# 28Pins_Schematic_V1I1.net
KiCad netlist of a schematic drawn in Altium Designer
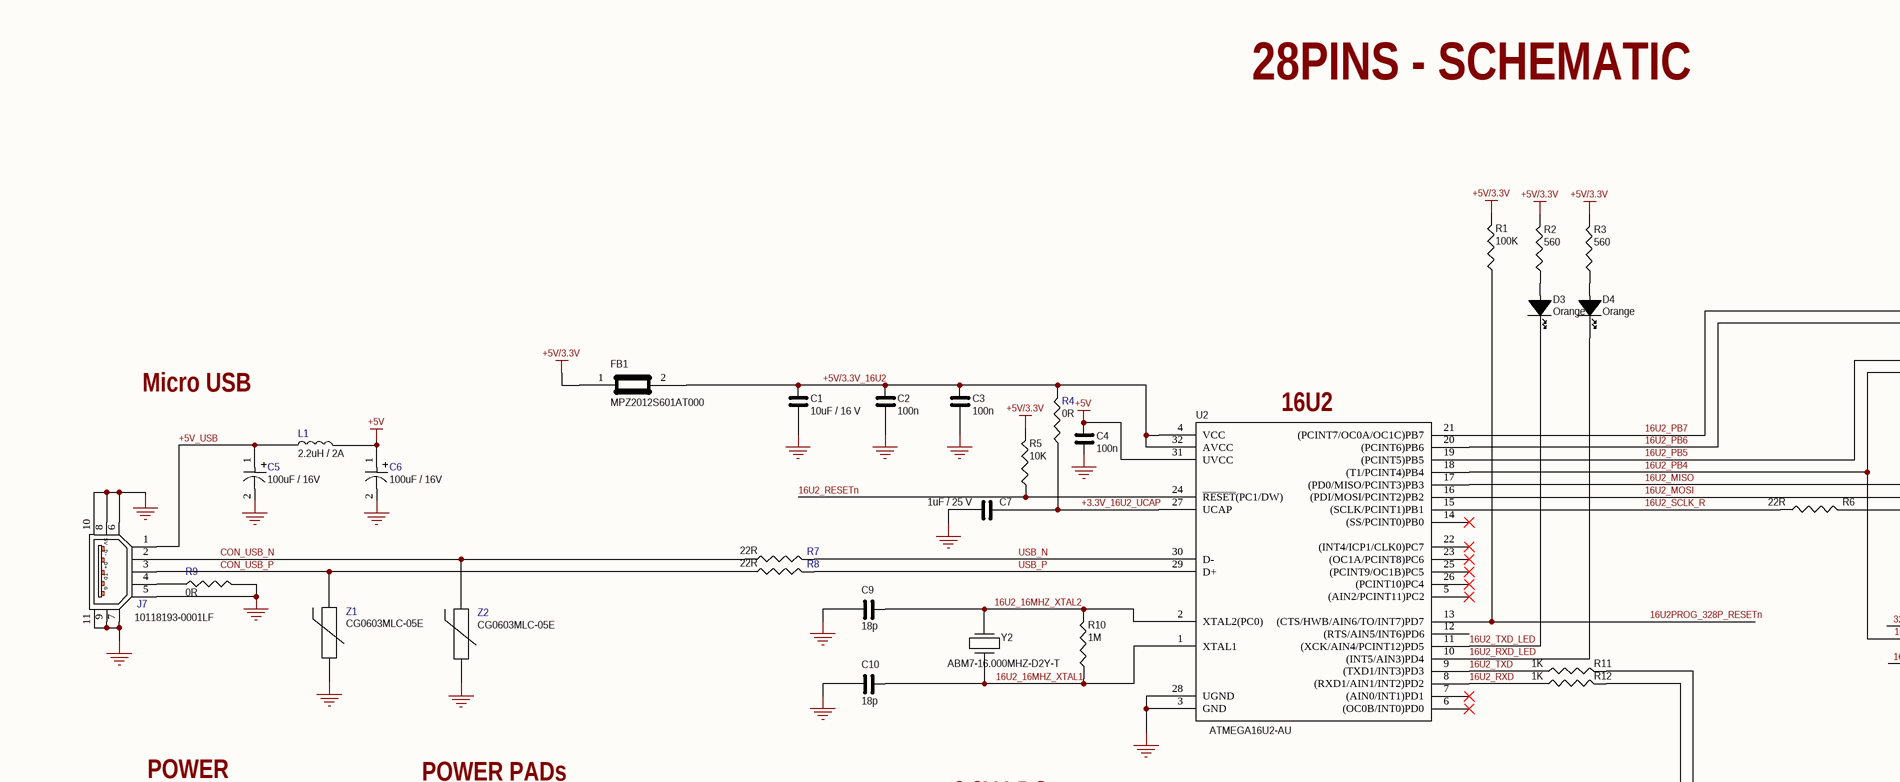
[diagram p0: 28Pins_Schematic_V1I1.SchDoc, top left]
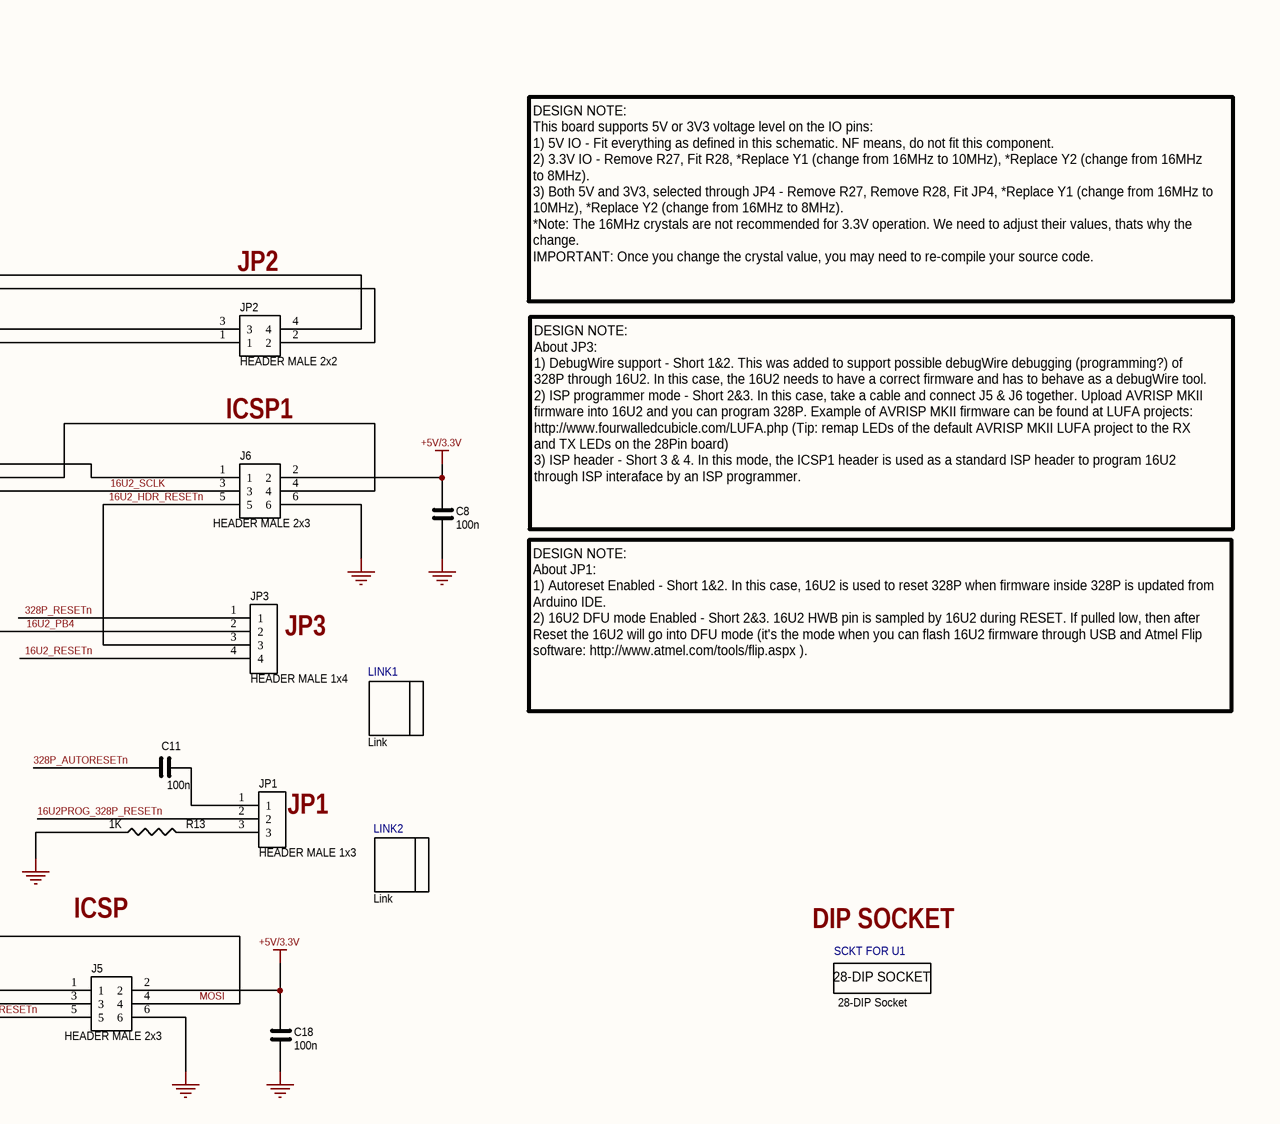
[diagram p1: 28Pins_Schematic_V1I1.SchDoc, top right]
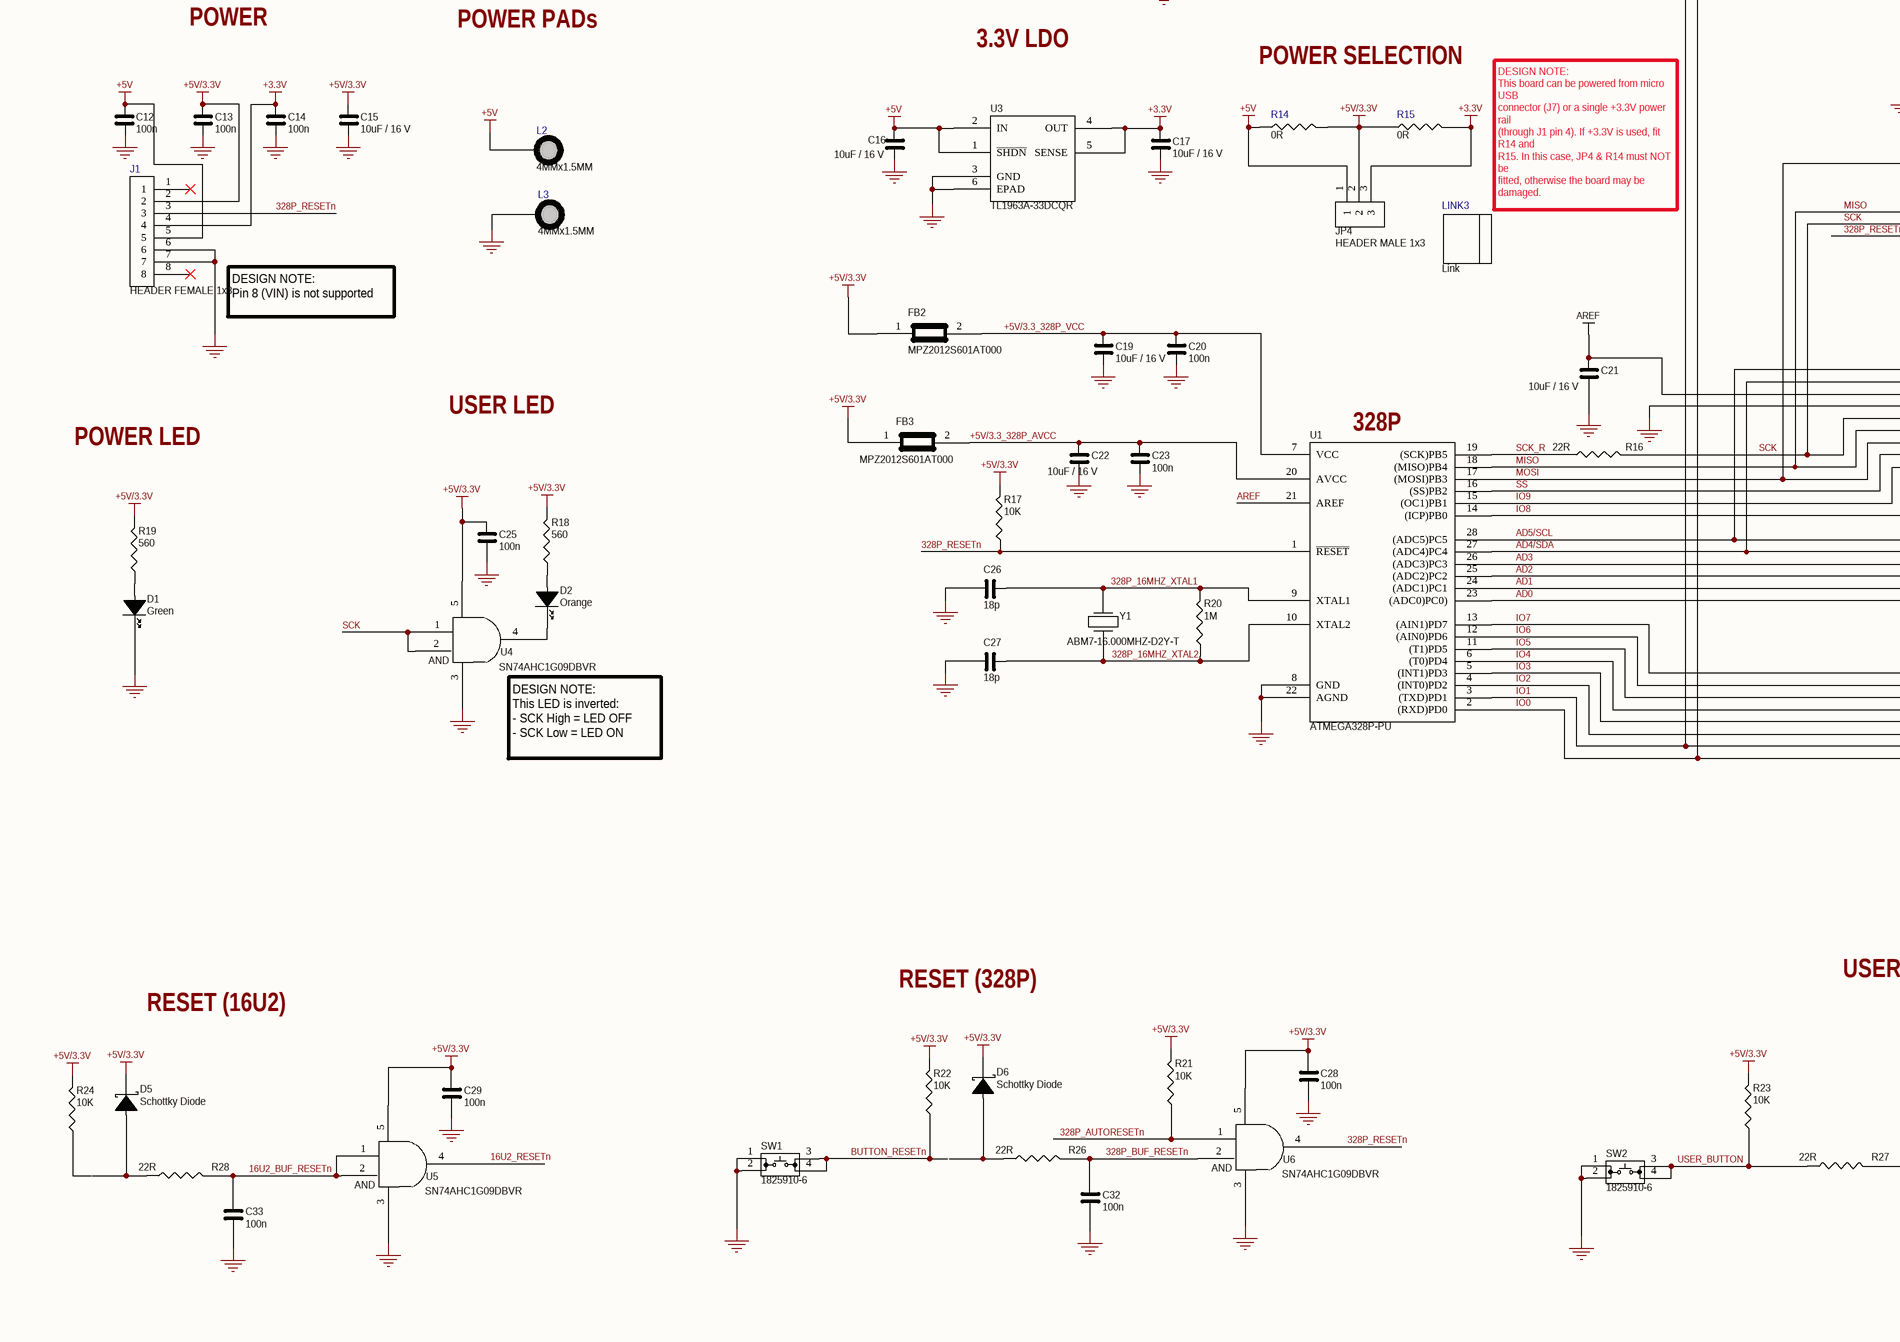
[diagram p2: 28Pins_Schematic_V1I1.SchDoc, bottom left]
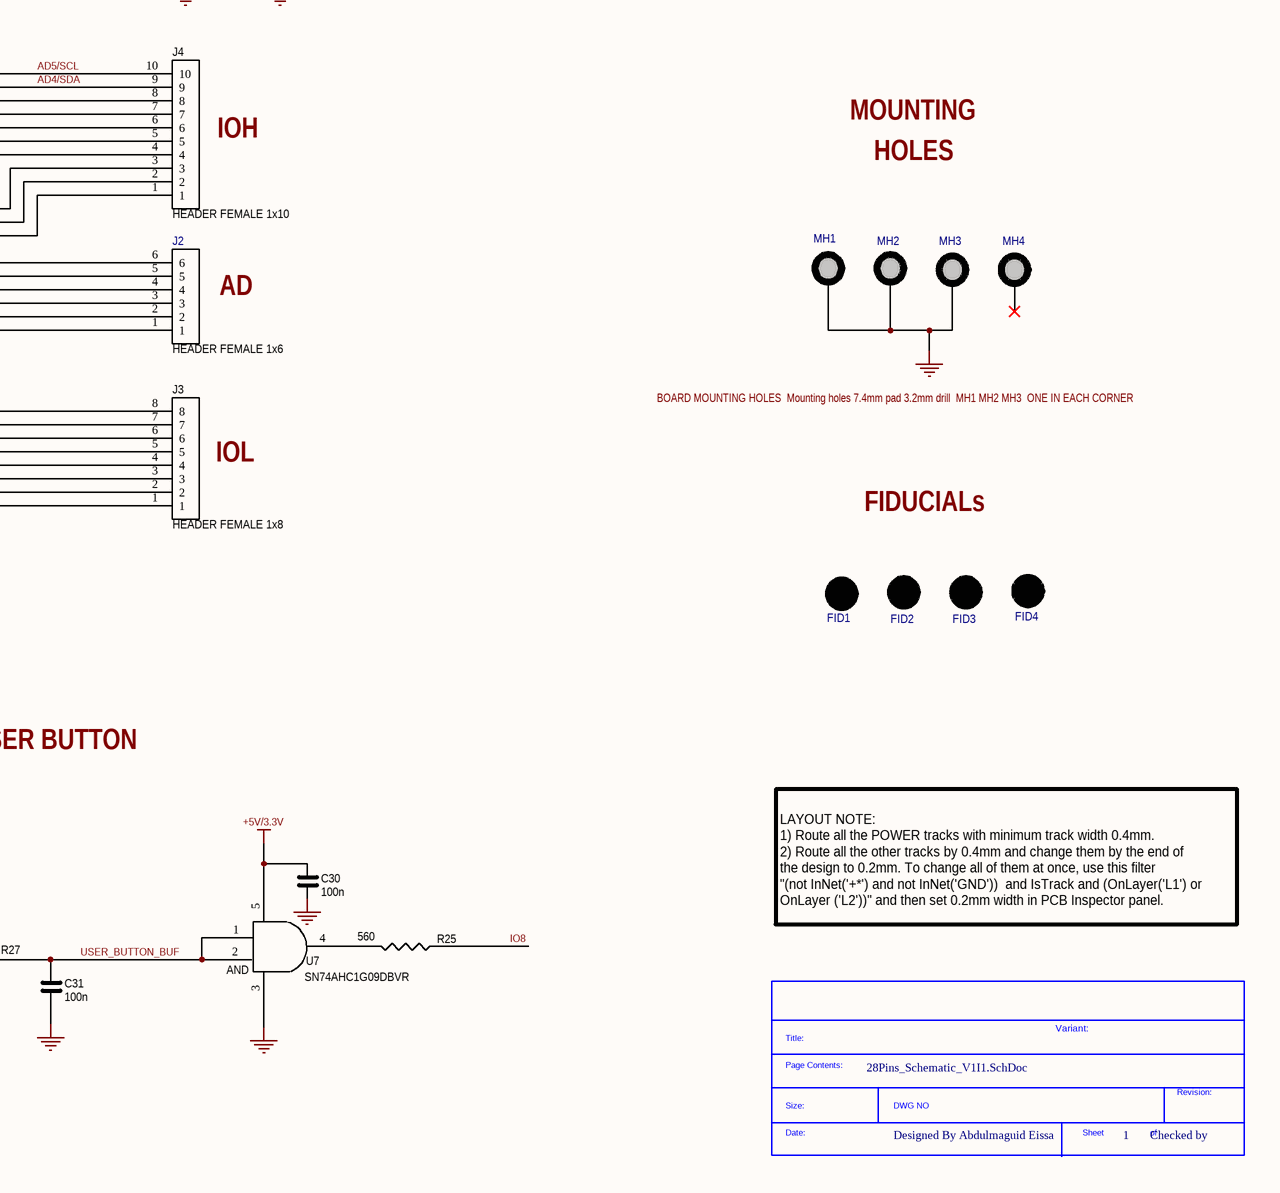
[diagram p3: 28Pins_Schematic_V1I1.SchDoc, bottom right]

(export (version "E")
  (design (tool "Eeschema 10.0.6"))
  (components
    (comp (ref "*") (value "SDTitleBlock") (libsource (lib "*") (part "SDTitleBlock")))
    (comp (ref "C1")
      (value "10uF / 16 V")
      (footprint "C0805")
      (libsource (lib "28Pins_Schematic_Lib") (part "10uF_CAP"))
    )
    (comp (ref "C2")
      (value "100n")
      (footprint "C0805")
      (libsource (lib "28Pins_Schematic_Lib") (part "0.1uF_CAP"))
    )
    (comp (ref "C3")
      (value "100n")
      (footprint "C0805")
      (libsource (lib "28Pins_Schematic_Lib") (part "0.1uF_CAP"))
    )
    (comp (ref "C4")
      (value "100n")
      (footprint "C0805")
      (libsource (lib "28Pins_Schematic_Lib") (part "0.1uF_CAP"))
    )
    (comp (ref "C5")
      (value "100uF / 16V")
      (footprint "C_ALU_C_SIZE")
      (libsource (lib "28Pins_Schematic_Lib") (part "100uF_PCAP"))
    )
    (comp (ref "C6")
      (value "100uF / 16V")
      (footprint "C_ALU_C_SIZE")
      (libsource (lib "28Pins_Schematic_Lib") (part "100uF_PCAP"))
    )
    (comp (ref "C7")
      (value "1uF / 25 V")
      (footprint "C0805")
      (libsource (lib "28Pins_Schematic_Lib") (part "1uF_CAP"))
    )
    (comp (ref "C8")
      (value "100n")
      (footprint "C0805")
      (libsource (lib "28Pins_Schematic_Lib") (part "0.1uF_CAP"))
    )
    (comp (ref "C9")
      (value "18p")
      (footprint "C0805")
      (libsource (lib "28Pins_Schematic_Lib") (part "18pF_CAP"))
    )
    (comp (ref "C10")
      (value "18p")
      (footprint "C0805")
      (libsource (lib "28Pins_Schematic_Lib") (part "18pF_CAP"))
    )
    (comp (ref "C11")
      (value "100n")
      (footprint "C0805")
      (libsource (lib "28Pins_Schematic_Lib") (part "0.1uF_CAP"))
    )
    (comp (ref "C12")
      (value "100n")
      (footprint "C0805")
      (libsource (lib "28Pins_Schematic_Lib") (part "0.1uF_CAP"))
    )
    (comp (ref "C13")
      (value "100n")
      (footprint "C0805")
      (libsource (lib "28Pins_Schematic_Lib") (part "0.1uF_CAP"))
    )
    (comp (ref "C14")
      (value "100n")
      (footprint "C0805")
      (libsource (lib "28Pins_Schematic_Lib") (part "0.1uF_CAP"))
    )
    (comp (ref "C15")
      (value "10uF / 16 V")
      (footprint "C0805")
      (libsource (lib "28Pins_Schematic_Lib") (part "10uF_CAP"))
    )
    (comp (ref "C16")
      (value "10uF / 16 V")
      (footprint "C0805")
      (libsource (lib "28Pins_Schematic_Lib") (part "10uF_CAP"))
    )
    (comp (ref "C17")
      (value "10uF / 16 V")
      (footprint "C0805")
      (libsource (lib "28Pins_Schematic_Lib") (part "10uF_CAP"))
    )
    (comp (ref "C18")
      (value "100n")
      (footprint "C0805")
      (libsource (lib "28Pins_Schematic_Lib") (part "0.1uF_CAP"))
    )
    (comp (ref "C19")
      (value "10uF / 16 V")
      (footprint "C0805")
      (libsource (lib "28Pins_Schematic_Lib") (part "10uF_CAP"))
    )
    (comp (ref "C20")
      (value "100n")
      (footprint "C0805")
      (libsource (lib "28Pins_Schematic_Lib") (part "0.1uF_CAP"))
    )
    (comp (ref "C21")
      (value "10uF / 16 V")
      (footprint "C0805")
      (libsource (lib "28Pins_Schematic_Lib") (part "10uF_CAP"))
    )
    (comp (ref "C22")
      (value "10uF / 16 V")
      (footprint "C0805")
      (libsource (lib "28Pins_Schematic_Lib") (part "10uF_CAP"))
    )
    (comp (ref "C23")
      (value "100n")
      (footprint "C0805")
      (libsource (lib "28Pins_Schematic_Lib") (part "0.1uF_CAP"))
    )
    (comp (ref "C25")
      (value "100n")
      (footprint "C0805")
      (libsource (lib "28Pins_Schematic_Lib") (part "0.1uF_CAP"))
    )
    (comp (ref "C26")
      (value "18p")
      (footprint "C0805")
      (libsource (lib "28Pins_Schematic_Lib") (part "18pF_CAP"))
    )
    (comp (ref "C27")
      (value "18p")
      (footprint "C0805")
      (libsource (lib "28Pins_Schematic_Lib") (part "18pF_CAP"))
    )
    (comp (ref "C28")
      (value "100n")
      (footprint "C0805")
      (libsource (lib "28Pins_Schematic_Lib") (part "0.1uF_CAP"))
    )
    (comp (ref "C29")
      (value "100n")
      (footprint "C0805")
      (libsource (lib "28Pins_Schematic_Lib") (part "0.1uF_CAP"))
    )
    (comp (ref "C30")
      (value "100n")
      (footprint "C0805")
      (libsource (lib "28Pins_Schematic_Lib") (part "0.1uF_CAP"))
    )
    (comp (ref "C31")
      (value "100n")
      (footprint "C0805")
      (libsource (lib "28Pins_Schematic_Lib") (part "0.1uF_CAP"))
    )
    (comp (ref "C32")
      (value "100n")
      (footprint "C0805")
      (libsource (lib "28Pins_Schematic_Lib") (part "0.1uF_CAP"))
    )
    (comp (ref "C33")
      (value "100n")
      (footprint "C0805")
      (libsource (lib "28Pins_Schematic_Lib") (part "0.1uF_CAP"))
    )
    (comp (ref "D1")
      (value "Green")
      (footprint "LED0603")
      (libsource (lib "28Pins_Schematic_Lib") (part "LED_Green"))
    )
    (comp (ref "D2")
      (value "Orange")
      (footprint "LED0603")
      (libsource (lib "28Pins_Schematic_Lib") (part "LED_Orange"))
    )
    (comp (ref "D3")
      (value "Orange")
      (footprint "LED0603")
      (libsource (lib "28Pins_Schematic_Lib") (part "LED_Orange"))
    )
    (comp (ref "D4")
      (value "Orange")
      (footprint "LED0603")
      (libsource (lib "28Pins_Schematic_Lib") (part "LED_Orange"))
    )
    (comp (ref "D5")
      (value "Schottky Diode")
      (footprint "SOD323")
      (description "Diode,Schottky Barrier,Fast,Vr 30V,If 200mA,Pkg SOD-323,Vf 0.52VDC,Trr 5ns")
      (fields
        (field (name "MANUFACTURER") "ON Semiconductor")
        (field (name "MANUFACTURER PART NUMBER") "BAT54HT1G")
      )
      (libsource (lib "28Pins_Schematic_Lib") (part "Schottky Diode"))
    )
    (comp (ref "D6")
      (value "Schottky Diode")
      (footprint "SOD323")
      (description "Diode,Schottky Barrier,Fast,Vr 30V,If 200mA,Pkg SOD-323,Vf 0.52VDC,Trr 5ns")
      (fields
        (field (name "MANUFACTURER") "ON Semiconductor")
        (field (name "MANUFACTURER PART NUMBER") "BAT54HT1G")
      )
      (libsource (lib "28Pins_Schematic_Lib") (part "Schottky Diode"))
    )
    (comp (ref "FB1")
      (value "MPZ2012S601AT000")
      (footprint "C0805")
      (libsource (lib "28Pins_Schematic_Lib") (part "Ferrite_Bead"))
    )
    (comp (ref "FB2")
      (value "MPZ2012S601AT000")
      (footprint "C0805")
      (libsource (lib "28Pins_Schematic_Lib") (part "Ferrite_Bead"))
    )
    (comp (ref "FB3")
      (value "MPZ2012S601AT000")
      (footprint "C0805")
      (libsource (lib "28Pins_Schematic_Lib") (part "Ferrite_Bead"))
    )
    (comp (ref "FID1")
      (value "FID_1mm")
      (footprint "FID_40x1120")
      (description "Fiducial 40mil diameter")
      (libsource (lib "28Pins_Schematic_Lib") (part "Fiducial"))
    )
    (comp (ref "FID2")
      (value "FID_1mm")
      (footprint "FID_40x1120")
      (description "Fiducial 40mil diameter")
      (libsource (lib "28Pins_Schematic_Lib") (part "Fiducial"))
    )
    (comp (ref "FID3")
      (value "FID_1mm")
      (footprint "FID_40x1120")
      (description "Fiducial 40mil diameter")
      (libsource (lib "28Pins_Schematic_Lib") (part "Fiducial"))
    )
    (comp (ref "FID4")
      (value "FID_1mm")
      (footprint "FID_40x1120")
      (description "Fiducial 40mil diameter")
      (libsource (lib "28Pins_Schematic_Lib") (part "Fiducial"))
    )
    (comp (ref "J1")
      (value "HEADER FEMALE 1x8")
      (footprint "1x8PIN_FEMALE_HDR")
      (libsource (lib "") (part "1x8Pin_Female_Hdr_1"))
    )
    (comp (ref "J2")
      (value "HEADER FEMALE 1x6")
      (footprint "1x6PIN_FEMALE_HDR")
      (libsource (lib "28Pins_Schematic_Lib") (part "1x6Pin_Female_Hdr"))
    )
    (comp (ref "J3")
      (value "HEADER FEMALE 1x8")
      (footprint "1x8PIN_FEMALE_HDR")
      (libsource (lib "28Pins_Schematic_Lib") (part "1x8Pin_Female_Hdr"))
    )
    (comp (ref "J4")
      (value "HEADER FEMALE 1x10")
      (footprint "1x10PIN_FEMALE_HDR")
      (libsource (lib "28Pins_Schematic_Lib") (part "10Pin_Female_Hdr"))
    )
    (comp (ref "J5")
      (value "HEADER MALE 2x3")
      (footprint "2x3PIN_MALE_HDR")
      (libsource (lib "28Pins_Schematic_Lib") (part "2x3Pin_Male_Hdr"))
    )
    (comp (ref "J6")
      (value "HEADER MALE 2x3")
      (footprint "2x3PIN_MALE_HDR")
      (libsource (lib "28Pins_Schematic_Lib") (part "2x3Pin_Male_Hdr"))
    )
    (comp (ref "J7")
      (value "10118193-0001LF")
      (footprint "USB_SOP")
      (description "Right Angle Surface Mount Mount Female USB Connector 100 V ac 1.8A")
      (fields (field (name "MANUFACTURER") "Amphenol ICC"))
      (libsource (lib "28Pins_Schematic_Lib") (part "10118193-0001LF"))
    )
    (comp (ref "JP1")
      (value "HEADER MALE 1x3")
      (footprint "1x3PIN_MALE_HDR")
      (libsource (lib "") (part "1x3Pin_Male_Hdr_1"))
    )
    (comp (ref "JP2")
      (value "HEADER MALE 2x2")
      (footprint "2x2PIN_MALE_HDR")
      (libsource (lib "28Pins_Schematic_Lib") (part "2x2Pin_Male_Hdr"))
    )
    (comp (ref "JP3")
      (value "HEADER MALE 1x4")
      (footprint "1x4PIN_MALE_HDR")
      (libsource (lib "28Pins_Schematic_Lib") (part "1x4Pin_Male_Hdr"))
    )
    (comp (ref "JP4")
      (value "HEADER MALE 1x3")
      (footprint "1x3PIN_MALE_HDR")
      (libsource (lib "28Pins_Schematic_Lib") (part "1x3Pin_Male_Hdr"))
    )
    (comp (ref "L1")
      (value "2.2uH / 2A")
      (footprint "L1210")
      (description "Inductor")
      (libsource (lib "28Pins_Schematic_Lib") (part "L1210R2R2MDWIT"))
    )
    (comp (ref "L2")
      (value "4MMx1.5MM")
      (footprint "PADS_WITH_WHOLE_4mmx1.5mm")
      (libsource (lib "28Pins_Schematic_Lib") (part "PAD_WITH_WHOLE_4MMx1.5MM"))
    )
    (comp (ref "L3")
      (value "4MMx1.5MM")
      (footprint "PADS_WITH_WHOLE_4mmx1.5mm")
      (libsource (lib "28Pins_Schematic_Lib") (part "PAD_WITH_WHOLE_4MMx1.5MM"))
    )
    (comp (ref "LINK1")
      (value "Link")
      (description "CONN JUMPER")
      (libsource (lib "28Pins_Schematic_Lib") (part "Link"))
    )
    (comp (ref "LINK2")
      (value "Link")
      (description "CONN JUMPER")
      (libsource (lib "28Pins_Schematic_Lib") (part "Link"))
    )
    (comp (ref "LINK3")
      (value "Link")
      (description "CONN JUMPER")
      (libsource (lib "28Pins_Schematic_Lib") (part "Link"))
    )
    (comp (ref "MH1")
      (value "Mounting Whole 3.4mmx3.2mm")
      (footprint "MOUNTING_WHOLE_NON_COPPER")
      (libsource (lib "28Pins_Schematic_Lib") (part "MOUNTING_WHOLE_NON_COPPER"))
    )
    (comp (ref "MH2")
      (value "Mounting Whole 3.4mmx3.2mm")
      (footprint "MOUNTING_WHOLE_NON_COPPER")
      (libsource (lib "28Pins_Schematic_Lib") (part "MOUNTING_WHOLE_NON_COPPER"))
    )
    (comp (ref "MH3")
      (value "Mounting Whole 3.4mmx3.2mm")
      (footprint "MOUNTING_WHOLE_NON_COPPER")
      (libsource (lib "28Pins_Schematic_Lib") (part "MOUNTING_WHOLE_NON_COPPER"))
    )
    (comp (ref "MH4")
      (value "Mounting Whole 3.4mmx3.2mm")
      (footprint "MOUNTING_WHOLE_NON_COPPER")
      (libsource (lib "28Pins_Schematic_Lib") (part "MOUNTING_WHOLE_NON_COPPER"))
    )
    (comp (ref "R1")
      (value "100K")
      (footprint "R0805")
      (libsource (lib "28Pins_Schematic_Lib") (part "100K_Resistor"))
    )
    (comp (ref "R2")
      (value "560")
      (footprint "R0805")
      (libsource (lib "28Pins_Schematic_Lib") (part "560_Resistor"))
    )
    (comp (ref "R3")
      (value "560")
      (footprint "R0805")
      (libsource (lib "28Pins_Schematic_Lib") (part "560_Resistor"))
    )
    (comp (ref "R4")
      (value "0R")
      (footprint "R0805")
      (libsource (lib "28Pins_Schematic_Lib") (part "0R_Resistor"))
    )
    (comp (ref "R5")
      (value "10K")
      (footprint "R0805")
      (libsource (lib "28Pins_Schematic_Lib") (part "10K_Resistor"))
    )
    (comp (ref "R6")
      (value "22R")
      (footprint "R0805")
      (libsource (lib "28Pins_Schematic_Lib") (part "22_Resistor"))
    )
    (comp (ref "R7")
      (value "22R")
      (footprint "R0805")
      (libsource (lib "28Pins_Schematic_Lib") (part "22_Resistor"))
    )
    (comp (ref "R8")
      (value "22R")
      (footprint "R0805")
      (libsource (lib "28Pins_Schematic_Lib") (part "22_Resistor"))
    )
    (comp (ref "R9")
      (value "0R")
      (footprint "R0805")
      (libsource (lib "28Pins_Schematic_Lib") (part "0R_Resistor"))
    )
    (comp (ref "R10")
      (value "1M")
      (footprint "R0805")
      (libsource (lib "28Pins_Schematic_Lib") (part "1M_Resistor"))
    )
    (comp (ref "R11")
      (value "1K")
      (footprint "R0805")
      (libsource (lib "28Pins_Schematic_Lib") (part "1K_Resistor"))
    )
    (comp (ref "R12")
      (value "1K")
      (footprint "R0805")
      (libsource (lib "28Pins_Schematic_Lib") (part "1K_Resistor"))
    )
    (comp (ref "R13")
      (value "1K")
      (footprint "R0805")
      (libsource (lib "28Pins_Schematic_Lib") (part "1K_Resistor"))
    )
    (comp (ref "R14")
      (value "0R")
      (footprint "R0805")
      (libsource (lib "28Pins_Schematic_Lib") (part "0R_Resistor"))
    )
    (comp (ref "R15")
      (value "0R")
      (footprint "R0805")
      (libsource (lib "28Pins_Schematic_Lib") (part "0R_Resistor"))
    )
    (comp (ref "R16")
      (value "22R")
      (footprint "R0805")
      (libsource (lib "28Pins_Schematic_Lib") (part "22_Resistor"))
    )
    (comp (ref "R17")
      (value "10K")
      (footprint "R0805")
      (libsource (lib "28Pins_Schematic_Lib") (part "10K_Resistor"))
    )
    (comp (ref "R18")
      (value "560")
      (footprint "R0805")
      (libsource (lib "28Pins_Schematic_Lib") (part "560_Resistor"))
    )
    (comp (ref "R19")
      (value "560")
      (footprint "R0805")
      (libsource (lib "28Pins_Schematic_Lib") (part "560_Resistor"))
    )
    (comp (ref "R20")
      (value "1M")
      (footprint "R0805")
      (libsource (lib "28Pins_Schematic_Lib") (part "1M_Resistor"))
    )
    (comp (ref "R21")
      (value "10K")
      (footprint "R0805")
      (libsource (lib "28Pins_Schematic_Lib") (part "10K_Resistor"))
    )
    (comp (ref "R22")
      (value "10K")
      (footprint "R0805")
      (libsource (lib "28Pins_Schematic_Lib") (part "10K_Resistor"))
    )
    (comp (ref "R23")
      (value "10K")
      (footprint "R0805")
      (libsource (lib "28Pins_Schematic_Lib") (part "10K_Resistor"))
    )
    (comp (ref "R24")
      (value "10K")
      (footprint "R0805")
      (libsource (lib "28Pins_Schematic_Lib") (part "10K_Resistor"))
    )
    (comp (ref "R25")
      (value "560")
      (footprint "R0805")
      (libsource (lib "28Pins_Schematic_Lib") (part "560_Resistor"))
    )
    (comp (ref "R26")
      (value "22R")
      (footprint "R0805")
      (libsource (lib "28Pins_Schematic_Lib") (part "22_Resistor"))
    )
    (comp (ref "R27")
      (value "22R")
      (footprint "R0805")
      (libsource (lib "28Pins_Schematic_Lib") (part "22_Resistor"))
    )
    (comp (ref "R28")
      (value "22R")
      (footprint "R0805")
      (libsource (lib "28Pins_Schematic_Lib") (part "22_Resistor"))
    )
    (comp (ref "SCKT FOR U1")
      (value "28-DIP Socket")
      (footprint "28-DIP_SCKT")
      (libsource (lib "28Pins_Schematic_Lib") (part "28Pin_DIP"))
    )
    (comp (ref "SW1")
      (value "1825910-6")
      (footprint "4PIN_BUTTON")
      (description "Push_Button")
      (libsource (lib "28Pins_Schematic_Lib") (part "4Pin_Push_Button"))
    )
    (comp (ref "SW2")
      (value "1825910-6")
      (footprint "4PIN_BUTTON")
      (description "Push_Button")
      (libsource (lib "28Pins_Schematic_Lib") (part "4Pin_Push_Button"))
    )
    (comp (ref "U1")
      (value "ATMEGA328P-PU")
      (footprint "28_DIP_U1")
      (description "ATMEGA328P-PU; 8 bit Microcontroller AVR 20MHz 1; 32kb Flash; 2kb RAM; I2C SPI 2")
      (fields (field (name "MANUFACTURER") "Microchip Technology Inc."))
      (libsource (lib "28Pins_Schematic_Lib") (part "ATMEGA328P-PU"))
    )
    (comp (ref "U2")
      (value "ATMEGA16U2-AU")
      (footprint "TQFP32")
      (libsource (lib "28Pins_Schematic_Lib") (part "ATMEGA16U2-AU"))
    )
    (comp (ref "U3")
      (value "TL1963A-33DCQR")
      (footprint "DCQR R-PDSO-G6")
      (libsource (lib "28Pins_Schematic_Lib") (part "Regulator"))
    )
    (comp (ref "U4")
      (value "SN74AHC1G09DBVR")
      (footprint "DBV_SOP_23_5")
      (libsource (lib "28Pins_Schematic_Lib") (part "AND gate"))
    )
    (comp (ref "U5")
      (value "SN74AHC1G09DBVR")
      (footprint "DBV_SOP_23_5")
      (libsource (lib "28Pins_Schematic_Lib") (part "AND gate"))
    )
    (comp (ref "U6")
      (value "SN74AHC1G09DBVR")
      (footprint "DBV_SOP_23_5")
      (libsource (lib "28Pins_Schematic_Lib") (part "AND gate"))
    )
    (comp (ref "U7")
      (value "SN74AHC1G09DBVR")
      (footprint "DBV_SOP_23_5")
      (libsource (lib "28Pins_Schematic_Lib") (part "AND gate"))
    )
    (comp (ref "Y1")
      (value "ABM7-16.000MHZ-D2Y-T")
      (footprint "AMB7_V1")
      (description "Crystal; Ceramic; 16.000MHZ; 18pf; 20ppm @ 25C; 30ppm -40+85C; 6.0 x 3.5 x 1.2mm; T/R")
      (fields (field (name "MANUFACTURER") "Abracon"))
      (libsource (lib "28Pins_Schematic_Lib") (part "ABM7-16.000MHZ-D2Y-T"))
    )
    (comp (ref "Y2")
      (value "ABM7-16.000MHZ-D2Y-T")
      (footprint "AMB7_V1")
      (description "Crystal; Ceramic; 16.000MHZ; 18pf; 20ppm @ 25C; 30ppm -40+85C; 6.0 x 3.5 x 1.2mm; T/R")
      (fields (field (name "MANUFACTURER") "Abracon"))
      (libsource (lib "28Pins_Schematic_Lib") (part "ABM7-16.000MHZ-D2Y-T"))
    )
    (comp (ref "Z1")
      (value "CG0603MLC-05E")
      (footprint "R0603")
      (description "Varistor; ESD Clamp Protector; 5 VDC; 20 Vclamp; IEC 61000-4-2 Level 4; 0603 SMD")
      (fields (field (name "MANUFACTURER") "Bourns"))
      (libsource (lib "28Pins_Schematic_Lib") (part "CG0603MLC-05E"))
    )
    (comp (ref "Z2")
      (value "CG0603MLC-05E")
      (footprint "R0603")
      (description "Varistor; ESD Clamp Protector; 5 VDC; 20 Vclamp; IEC 61000-4-2 Level 4; 0603 SMD")
      (fields (field (name "MANUFACTURER") "Bourns"))
      (libsource (lib "28Pins_Schematic_Lib") (part "CG0603MLC-05E"))
    )
  )
  (nets
    (net (code "1") (name "+3.3V") (class "Default")
      (node (ref "C14") (pin "2") (pinfunction "2_2") (pintype "passive"))
      (node (ref "C17") (pin "2") (pinfunction "2_2") (pintype "passive"))
      (node (ref "J1") (pin "4") (pinfunction "4_4") (pintype "passive"))
      (node (ref "JP4") (pin "3") (pinfunction "3_3") (pintype "passive"))
      (node (ref "R15") (pin "2") (pinfunction "2_2") (pintype "passive"))
      (node (ref "U3") (pin "4") (pinfunction "OUT_4") (pintype "passive"))
      (node (ref "U3") (pin "5") (pinfunction "SENSE_5") (pintype "passive"))
    )
    (net (code "2") (name "+5V") (class "Default")
      (node (ref "C12") (pin "1") (pinfunction "1_1") (pintype "passive"))
      (node (ref "C16") (pin "2") (pinfunction "2_2") (pintype "passive"))
      (node (ref "C4") (pin "2") (pinfunction "2_2") (pintype "passive"))
      (node (ref "C6") (pin "1") (pinfunction "1_1") (pintype "passive"))
      (node (ref "J1") (pin "5") (pinfunction "5_5") (pintype "passive"))
      (node (ref "JP4") (pin "1") (pinfunction "1_1") (pintype "passive"))
      (node (ref "L1") (pin "2") (pinfunction "2_2") (pintype "passive"))
      (node (ref "L2") (pin "1") (pinfunction "1_1") (pintype "passive"))
      (node (ref "R14") (pin "1") (pinfunction "1_1") (pintype "passive"))
      (node (ref "U2") (pin "31") (pinfunction "UVCC_31") (pintype "passive"))
      (node (ref "U3") (pin "1") (pinfunction "~{SHDN}_1") (pintype "passive"))
      (node (ref "U3") (pin "2") (pinfunction "IN_2") (pintype "passive"))
    )
    (net (code "3") (name "+5V{slash}3.3V") (class "Default")
      (node (ref "C13") (pin "2") (pinfunction "2_2") (pintype "passive"))
      (node (ref "C15") (pin "2") (pinfunction "2_2") (pintype "passive"))
      (node (ref "C18") (pin "2") (pinfunction "2_2") (pintype "passive"))
      (node (ref "C25") (pin "2") (pinfunction "2_2") (pintype "passive"))
      (node (ref "C28") (pin "2") (pinfunction "2_2") (pintype "passive"))
      (node (ref "C29") (pin "2") (pinfunction "2_2") (pintype "passive"))
      (node (ref "C30") (pin "2") (pinfunction "2_2") (pintype "passive"))
      (node (ref "C8") (pin "2") (pinfunction "2_2") (pintype "passive"))
      (node (ref "D5") (pin "1") (pinfunction "Cathode_1") (pintype "passive"))
      (node (ref "D6") (pin "1") (pinfunction "Cathode_1") (pintype "passive"))
      (node (ref "FB1") (pin "1") (pinfunction "1_1") (pintype "passive"))
      (node (ref "FB2") (pin "1") (pinfunction "1_1") (pintype "passive"))
      (node (ref "FB3") (pin "1") (pinfunction "1_1") (pintype "passive"))
      (node (ref "J1") (pin "2") (pinfunction "2_2") (pintype "passive"))
      (node (ref "J5") (pin "2") (pinfunction "2_2") (pintype "passive"))
      (node (ref "J6") (pin "2") (pinfunction "2_2") (pintype "passive"))
      (node (ref "JP4") (pin "2") (pinfunction "2_2") (pintype "passive"))
      (node (ref "R1") (pin "2") (pinfunction "2_2") (pintype "passive"))
      (node (ref "R14") (pin "2") (pinfunction "2_2") (pintype "passive"))
      (node (ref "R15") (pin "1") (pinfunction "1_1") (pintype "passive"))
      (node (ref "R17") (pin "2") (pinfunction "2_2") (pintype "passive"))
      (node (ref "R18") (pin "2") (pinfunction "2_2") (pintype "passive"))
      (node (ref "R19") (pin "2") (pinfunction "2_2") (pintype "passive"))
      (node (ref "R2") (pin "2") (pinfunction "2_2") (pintype "passive"))
      (node (ref "R21") (pin "2") (pinfunction "2_2") (pintype "passive"))
      (node (ref "R22") (pin "2") (pinfunction "2_2") (pintype "passive"))
      (node (ref "R23") (pin "2") (pinfunction "2_2") (pintype "passive"))
      (node (ref "R24") (pin "2") (pinfunction "2_2") (pintype "passive"))
      (node (ref "R3") (pin "2") (pinfunction "2_2") (pintype "passive"))
      (node (ref "R5") (pin "2") (pinfunction "2_2") (pintype "passive"))
      (node (ref "U4") (pin "5") (pinfunction "5_5") (pintype "passive"))
      (node (ref "U5") (pin "5") (pinfunction "5_5") (pintype "passive"))
      (node (ref "U6") (pin "5") (pinfunction "5_5") (pintype "passive"))
      (node (ref "U7") (pin "5") (pinfunction "5_5") (pintype "passive"))
    )
    (net (code "4") (name "/+3.3V_16U2_UCAP") (class "Default")
      (node (ref "C7") (pin "2") (pinfunction "2_2") (pintype "passive"))
      (node (ref "R4") (pin "1") (pinfunction "1_1") (pintype "passive"))
      (node (ref "U2") (pin "27") (pinfunction "UCAP_27") (pintype "passive"))
    )
    (net (code "5") (name "/+5V_USB") (class "Default")
      (node (ref "C5") (pin "1") (pinfunction "1_1") (pintype "passive"))
      (node (ref "J7") (pin "1") (pinfunction "1_1") (pintype "passive"))
      (node (ref "L1") (pin "1") (pinfunction "1_1") (pintype "passive"))
    )
    (net (code "6") (name "/+5V{slash}3.3V_16U2") (class "Default")
      (node (ref "C1") (pin "2") (pinfunction "2_2") (pintype "passive"))
      (node (ref "C2") (pin "2") (pinfunction "2_2") (pintype "passive"))
      (node (ref "C3") (pin "2") (pinfunction "2_2") (pintype "passive"))
      (node (ref "FB1") (pin "2") (pinfunction "2_2") (pintype "passive"))
      (node (ref "R4") (pin "2") (pinfunction "2_2") (pintype "passive"))
      (node (ref "U2") (pin "32") (pinfunction "AVCC_32") (pintype "passive"))
      (node (ref "U2") (pin "4") (pinfunction "VCC_4") (pintype "passive"))
    )
    (net (code "7") (name "/+5V{slash}3.3_328P_AVCC") (class "Default")
      (node (ref "C22") (pin "2") (pinfunction "2_2") (pintype "passive"))
      (node (ref "C23") (pin "2") (pinfunction "2_2") (pintype "passive"))
      (node (ref "FB3") (pin "2") (pinfunction "2_2") (pintype "passive"))
      (node (ref "U1") (pin "20") (pinfunction "AVCC_20") (pintype "passive"))
    )
    (net (code "8") (name "/+5V{slash}3.3_328P_VCC") (class "Default")
      (node (ref "C19") (pin "2") (pinfunction "2_2") (pintype "passive"))
      (node (ref "C20") (pin "2") (pinfunction "2_2") (pintype "passive"))
      (node (ref "FB2") (pin "2") (pinfunction "2_2") (pintype "passive"))
      (node (ref "U1") (pin "7") (pinfunction "VCC_7") (pintype "passive"))
    )
    (net (code "9") (name "/16U2PROG_328P_RESETn") (class "Default")
      (node (ref "JP1") (pin "2") (pinfunction "2_2") (pintype "passive"))
      (node (ref "R1") (pin "1") (pinfunction "1_1") (pintype "passive"))
      (node (ref "U2") (pin "13") (pinfunction "(CTS/HWB/AIN6/TO/INT7)PD7_13") (pintype "passive"))
    )
    (net (code "10") (name "/16U2_16MHZ_XTAL1") (class "Default")
      (node (ref "C10") (pin "2") (pinfunction "2_2") (pintype "passive"))
      (node (ref "R10") (pin "1") (pinfunction "1_1") (pintype "passive"))
      (node (ref "U2") (pin "1") (pinfunction "XTAL1_1") (pintype "passive"))
      (node (ref "Y2") (pin "1") (pinfunction "1_1") (pintype "passive"))
    )
    (net (code "11") (name "/16U2_16MHZ_XTAL2") (class "Default")
      (node (ref "C9") (pin "2") (pinfunction "2_2") (pintype "passive"))
      (node (ref "R10") (pin "2") (pinfunction "2_2") (pintype "passive"))
      (node (ref "U2") (pin "2") (pinfunction "XTAL2(PC0)_2") (pintype "passive"))
      (node (ref "Y2") (pin "2") (pinfunction "2_2") (pintype "passive"))
    )
    (net (code "12") (name "/16U2_BUF_RESETn") (class "Default")
      (node (ref "C33") (pin "2") (pinfunction "2_2") (pintype "passive"))
      (node (ref "R28") (pin "2") (pinfunction "2_2") (pintype "passive"))
      (node (ref "U5") (pin "1") (pinfunction "1_1") (pintype "passive"))
      (node (ref "U5") (pin "2") (pinfunction "2_2") (pintype "passive"))
    )
    (net (code "13") (name "/16U2_HDR_RESETn") (class "Default")
      (node (ref "J6") (pin "5") (pinfunction "5_5") (pintype "passive"))
      (node (ref "JP3") (pin "3") (pinfunction "3_3") (pintype "passive"))
    )
    (net (code "14") (name "/16U2_MISO") (class "Default")
      (node (ref "J6") (pin "1") (pinfunction "1_1") (pintype "passive"))
      (node (ref "U2") (pin "17") (pinfunction "(PD0/MISO/PCINT3)PB3_17") (pintype "passive"))
    )
    (net (code "15") (name "/16U2_MOSI") (class "Default")
      (node (ref "J6") (pin "4") (pinfunction "4_4") (pintype "passive"))
      (node (ref "U2") (pin "16") (pinfunction "(PDI/MOSI/PCINT2)PB2_16") (pintype "passive"))
    )
    (net (code "16") (name "/16U2_PB4") (class "Default")
      (node (ref "JP2") (pin "1") (pinfunction "1_1") (pintype "passive"))
      (node (ref "JP3") (pin "2") (pinfunction "2_2") (pintype "passive"))
      (node (ref "U2") (pin "18") (pinfunction "(T1/PCINT4)PB4_18") (pintype "passive"))
    )
    (net (code "17") (name "/16U2_PB5") (class "Default")
      (node (ref "JP2") (pin "3") (pinfunction "3_3") (pintype "passive"))
      (node (ref "U2") (pin "19") (pinfunction "(PCINT5)PB5_19") (pintype "passive"))
    )
    (net (code "18") (name "/16U2_PB6") (class "Default")
      (node (ref "JP2") (pin "2") (pinfunction "2_2") (pintype "passive"))
      (node (ref "U2") (pin "20") (pinfunction "(PCINT6)PB6_20") (pintype "passive"))
    )
    (net (code "19") (name "/16U2_PB7") (class "Default")
      (node (ref "JP2") (pin "4") (pinfunction "4_4") (pintype "passive"))
      (node (ref "U2") (pin "21") (pinfunction "(PCINT7/OC0A/OC1C)PB7_21") (pintype "passive"))
    )
    (net (code "20") (name "/16U2_RESETn") (class "Default")
      (node (ref "JP3") (pin "4") (pinfunction "4_4") (pintype "passive"))
      (node (ref "R5") (pin "1") (pinfunction "1_1") (pintype "passive"))
      (node (ref "U2") (pin "24") (pinfunction "~{RESET}(PC1/DW)_24") (pintype "passive"))
      (node (ref "U5") (pin "4") (pinfunction "4_4") (pintype "passive"))
    )
    (net (code "21") (name "/16U2_RXD") (class "Default")
      (node (ref "R12") (pin "1") (pinfunction "1_1") (pintype "passive"))
      (node (ref "U2") (pin "8") (pinfunction "(RXD1/AIN1/INT2)PD2_8") (pintype "passive"))
    )
    (net (code "22") (name "/16U2_RXD_LED") (class "Default")
      (node (ref "D4") (pin "1") (pinfunction "Cathode_1") (pintype "passive"))
      (node (ref "U2") (pin "10") (pinfunction "(INT5/AIN3)PD4_10") (pintype "passive"))
    )
    (net (code "23") (name "/16U2_SCLK") (class "Default")
      (node (ref "J6") (pin "3") (pinfunction "3_3") (pintype "passive"))
      (node (ref "R6") (pin "2") (pinfunction "2_2") (pintype "passive"))
    )
    (net (code "24") (name "/16U2_SCLK_R") (class "Default")
      (node (ref "R6") (pin "1") (pinfunction "1_1") (pintype "passive"))
      (node (ref "U2") (pin "15") (pinfunction "(SCLK/PCINT1)PB1_15") (pintype "passive"))
    )
    (net (code "25") (name "/16U2_TXD") (class "Default")
      (node (ref "R11") (pin "1") (pinfunction "1_1") (pintype "passive"))
      (node (ref "U2") (pin "9") (pinfunction "(TXD1/INT3)PD3_9") (pintype "passive"))
    )
    (net (code "26") (name "/16U2_TXD_LED") (class "Default")
      (node (ref "D3") (pin "1") (pinfunction "Cathode_1") (pintype "passive"))
      (node (ref "U2") (pin "11") (pinfunction "(XCK/AIN4/PCINT12)PD5_11") (pintype "passive"))
    )
    (net (code "27") (name "/328P_16MHZ_XTAL1") (class "Default")
      (node (ref "C26") (pin "2") (pinfunction "2_2") (pintype "passive"))
      (node (ref "R20") (pin "2") (pinfunction "2_2") (pintype "passive"))
      (node (ref "U1") (pin "9") (pinfunction "XTAL1_9") (pintype "passive"))
      (node (ref "Y1") (pin "2") (pinfunction "2_2") (pintype "passive"))
    )
    (net (code "28") (name "/328P_16MHZ_XTAL2") (class "Default")
      (node (ref "C27") (pin "2") (pinfunction "2_2") (pintype "passive"))
      (node (ref "R20") (pin "1") (pinfunction "1_1") (pintype "passive"))
      (node (ref "U1") (pin "10") (pinfunction "XTAL2_10") (pintype "passive"))
      (node (ref "Y1") (pin "1") (pinfunction "1_1") (pintype "passive"))
    )
    (net (code "29") (name "/328P_AUTORESETn") (class "Default")
      (node (ref "C11") (pin "2") (pinfunction "2_2") (pintype "passive"))
      (node (ref "R21") (pin "1") (pinfunction "1_1") (pintype "passive"))
      (node (ref "U6") (pin "1") (pinfunction "1_1") (pintype "passive"))
    )
    (net (code "30") (name "/328P_BUF_RESETn") (class "Default")
      (node (ref "C32") (pin "2") (pinfunction "2_2") (pintype "passive"))
      (node (ref "R26") (pin "2") (pinfunction "2_2") (pintype "passive"))
      (node (ref "U6") (pin "2") (pinfunction "2_2") (pintype "passive"))
    )
    (net (code "31") (name "/328P_RESETn") (class "Default")
      (node (ref "J1") (pin "3") (pinfunction "3_3") (pintype "passive"))
      (node (ref "J5") (pin "5") (pinfunction "5_5") (pintype "passive"))
      (node (ref "JP3") (pin "1") (pinfunction "1_1") (pintype "passive"))
      (node (ref "R17") (pin "1") (pinfunction "1_1") (pintype "passive"))
      (node (ref "U1") (pin "1") (pinfunction "~{RESET}_1") (pintype "passive"))
      (node (ref "U6") (pin "4") (pinfunction "4_4") (pintype "passive"))
    )
    (net (code "32") (name "/AD0") (class "Default")
      (node (ref "J2") (pin "1") (pinfunction "1_1") (pintype "passive"))
      (node (ref "U1") (pin "23") (pinfunction "(ADC0)PC0)_23") (pintype "passive"))
    )
    (net (code "33") (name "/AD1") (class "Default")
      (node (ref "J2") (pin "2") (pinfunction "2_2") (pintype "passive"))
      (node (ref "U1") (pin "24") (pinfunction "(ADC1)PC1_24") (pintype "passive"))
    )
    (net (code "34") (name "/AD2") (class "Default")
      (node (ref "J2") (pin "3") (pinfunction "3_3") (pintype "passive"))
      (node (ref "U1") (pin "25") (pinfunction "(ADC2)PC2_25") (pintype "passive"))
    )
    (net (code "35") (name "/AD3") (class "Default")
      (node (ref "J2") (pin "4") (pinfunction "4_4") (pintype "passive"))
      (node (ref "U1") (pin "26") (pinfunction "(ADC3)PC3_26") (pintype "passive"))
    )
    (net (code "36") (name "/AD4{slash}SDA") (class "Default")
      (node (ref "J2") (pin "5") (pinfunction "5_5") (pintype "passive"))
      (node (ref "J4") (pin "9") (pinfunction "9_9") (pintype "passive"))
      (node (ref "U1") (pin "27") (pinfunction "(ADC4)PC4_27") (pintype "passive"))
    )
    (net (code "37") (name "/AD5{slash}SCL") (class "Default")
      (node (ref "J2") (pin "6") (pinfunction "6_6") (pintype "passive"))
      (node (ref "J4") (pin "10") (pinfunction "10_10") (pintype "passive"))
      (node (ref "U1") (pin "28") (pinfunction "(ADC5)PC5_28") (pintype "passive"))
    )
    (net (code "38") (name "/BUTTON_RESETn") (class "Default")
      (node (ref "R22") (pin "1") (pinfunction "1_1") (pintype "passive"))
      (node (ref "SW1") (pin "3") (pinfunction "3_3") (pintype "passive"))
      (node (ref "SW1") (pin "4") (pinfunction "4_4") (pintype "passive"))
    )
    (net (code "39") (name "/CON_USB_N") (class "Default")
      (node (ref "J7") (pin "2") (pinfunction "2_2") (pintype "passive"))
      (node (ref "R7") (pin "1") (pinfunction "1_1") (pintype "passive"))
      (node (ref "Z2") (pin "2") (pinfunction "2_2") (pintype "passive"))
    )
    (net (code "40") (name "/CON_USB_P") (class "Default")
      (node (ref "J7") (pin "3") (pinfunction "3_3") (pintype "passive"))
      (node (ref "R8") (pin "1") (pinfunction "1_1") (pintype "passive"))
      (node (ref "Z1") (pin "2") (pinfunction "2_2") (pintype "passive"))
    )
    (net (code "41") (name "/IO0") (class "Default")
      (node (ref "J3") (pin "1") (pinfunction "1_1") (pintype "passive"))
      (node (ref "R11") (pin "2") (pinfunction "2_2") (pintype "passive"))
      (node (ref "U1") (pin "2") (pinfunction "(RXD)PD0_2") (pintype "passive"))
    )
    (net (code "42") (name "/IO1") (class "Default")
      (node (ref "J3") (pin "2") (pinfunction "2_2") (pintype "passive"))
      (node (ref "R12") (pin "2") (pinfunction "2_2") (pintype "passive"))
      (node (ref "U1") (pin "3") (pinfunction "(TXD)PD1_3") (pintype "passive"))
    )
    (net (code "43") (name "/IO2") (class "Default")
      (node (ref "J3") (pin "3") (pinfunction "3_3") (pintype "passive"))
      (node (ref "U1") (pin "4") (pinfunction "(INT0)PD2_4") (pintype "passive"))
    )
    (net (code "44") (name "/IO3") (class "Default")
      (node (ref "J3") (pin "4") (pinfunction "4_4") (pintype "passive"))
      (node (ref "U1") (pin "5") (pinfunction "(INT1)PD3_5") (pintype "passive"))
    )
    (net (code "45") (name "/IO4") (class "Default")
      (node (ref "J3") (pin "5") (pinfunction "5_5") (pintype "passive"))
      (node (ref "U1") (pin "6") (pinfunction "(T0)PD4_6") (pintype "passive"))
    )
    (net (code "46") (name "/IO5") (class "Default")
      (node (ref "J3") (pin "6") (pinfunction "6_6") (pintype "passive"))
      (node (ref "U1") (pin "11") (pinfunction "(T1)PD5_11") (pintype "passive"))
    )
    (net (code "47") (name "/IO6") (class "Default")
      (node (ref "J3") (pin "7") (pinfunction "7_7") (pintype "passive"))
      (node (ref "U1") (pin "12") (pinfunction "(AIN0)PD6_12") (pintype "passive"))
    )
    (net (code "48") (name "/IO7") (class "Default")
      (node (ref "J3") (pin "8") (pinfunction "8_8") (pintype "passive"))
      (node (ref "U1") (pin "13") (pinfunction "(AIN1)PD7_13") (pintype "passive"))
    )
    (net (code "49") (name "/IO8") (class "Default")
      (node (ref "J4") (pin "1") (pinfunction "1_1") (pintype "passive"))
      (node (ref "R25") (pin "1") (pinfunction "1_1") (pintype "passive"))
      (node (ref "U1") (pin "14") (pinfunction "(ICP)PB0_14") (pintype "passive"))
    )
    (net (code "50") (name "/IO9") (class "Default")
      (node (ref "J4") (pin "2") (pinfunction "2_2") (pintype "passive"))
      (node (ref "U1") (pin "15") (pinfunction "(OC1)PB1_15") (pintype "passive"))
    )
    (net (code "51") (name "/MISO") (class "Default")
      (node (ref "J4") (pin "5") (pinfunction "5_5") (pintype "passive"))
      (node (ref "J5") (pin "1") (pinfunction "1_1") (pintype "passive"))
      (node (ref "U1") (pin "18") (pinfunction "(MISO)PB4_18") (pintype "passive"))
    )
    (net (code "52") (name "/MOSI") (class "Default")
      (node (ref "J4") (pin "4") (pinfunction "4_4") (pintype "passive"))
      (node (ref "J5") (pin "4") (pinfunction "4_4") (pintype "passive"))
      (node (ref "U1") (pin "17") (pinfunction "(MOSI)PB3_17") (pintype "passive"))
    )
    (net (code "53") (name "/SCK") (class "Default")
      (node (ref "J4") (pin "6") (pinfunction "6_6") (pintype "passive"))
      (node (ref "J5") (pin "3") (pinfunction "3_3") (pintype "passive"))
      (node (ref "R16") (pin "2") (pinfunction "2_2") (pintype "passive"))
      (node (ref "U4") (pin "1") (pinfunction "1_1") (pintype "passive"))
      (node (ref "U4") (pin "2") (pinfunction "2_2") (pintype "passive"))
    )
    (net (code "54") (name "/SCK_R") (class "Default")
      (node (ref "R16") (pin "1") (pinfunction "1_1") (pintype "passive"))
      (node (ref "U1") (pin "19") (pinfunction "(SCK)PB5_19") (pintype "passive"))
    )
    (net (code "55") (name "/SS") (class "Default")
      (node (ref "J4") (pin "3") (pinfunction "3_3") (pintype "passive"))
      (node (ref "U1") (pin "16") (pinfunction "(SS)PB2_16") (pintype "passive"))
    )
    (net (code "56") (name "/USB_N") (class "Default")
      (node (ref "R7") (pin "2") (pinfunction "2_2") (pintype "passive"))
      (node (ref "U2") (pin "30") (pinfunction "D-_30") (pintype "passive"))
    )
    (net (code "57") (name "/USB_P") (class "Default")
      (node (ref "R8") (pin "2") (pinfunction "2_2") (pintype "passive"))
      (node (ref "U2") (pin "29") (pinfunction "D+_29") (pintype "passive"))
    )
    (net (code "58") (name "/USER_BUTTON") (class "Default")
      (node (ref "R23") (pin "1") (pinfunction "1_1") (pintype "passive"))
      (node (ref "R27") (pin "1") (pinfunction "1_1") (pintype "passive"))
      (node (ref "SW2") (pin "3") (pinfunction "3_3") (pintype "passive"))
      (node (ref "SW2") (pin "4") (pinfunction "4_4") (pintype "passive"))
    )
    (net (code "59") (name "/USER_BUTTON_BUF") (class "Default")
      (node (ref "C31") (pin "2") (pinfunction "2_2") (pintype "passive"))
      (node (ref "R27") (pin "2") (pinfunction "2_2") (pintype "passive"))
      (node (ref "U7") (pin "1") (pinfunction "1_1") (pintype "passive"))
      (node (ref "U7") (pin "2") (pinfunction "2_2") (pintype "passive"))
    )
    (net (code "60") (name "AREF") (class "Default")
      (node (ref "C21") (pin "2") (pinfunction "2_2") (pintype "passive"))
      (node (ref "J4") (pin "8") (pinfunction "8_8") (pintype "passive"))
      (node (ref "U1") (pin "21") (pinfunction "AREF_21") (pintype "passive"))
    )
    (net (code "61") (name "GND") (class "Default")
      (node (ref "C1") (pin "1") (pinfunction "1_1") (pintype "passive"))
      (node (ref "C10") (pin "1") (pinfunction "1_1") (pintype "passive"))
      (node (ref "C12") (pin "2") (pinfunction "2_2") (pintype "passive"))
      (node (ref "C13") (pin "1") (pinfunction "1_1") (pintype "passive"))
      (node (ref "C14") (pin "1") (pinfunction "1_1") (pintype "passive"))
      (node (ref "C15") (pin "1") (pinfunction "1_1") (pintype "passive"))
      (node (ref "C16") (pin "1") (pinfunction "1_1") (pintype "passive"))
      (node (ref "C17") (pin "1") (pinfunction "1_1") (pintype "passive"))
      (node (ref "C18") (pin "1") (pinfunction "1_1") (pintype "passive"))
      (node (ref "C19") (pin "1") (pinfunction "1_1") (pintype "passive"))
      (node (ref "C2") (pin "1") (pinfunction "1_1") (pintype "passive"))
      (node (ref "C20") (pin "1") (pinfunction "1_1") (pintype "passive"))
      (node (ref "C21") (pin "1") (pinfunction "1_1") (pintype "passive"))
      (node (ref "C22") (pin "1") (pinfunction "1_1") (pintype "passive"))
      (node (ref "C23") (pin "1") (pinfunction "1_1") (pintype "passive"))
      (node (ref "C25") (pin "1") (pinfunction "1_1") (pintype "passive"))
      (node (ref "C26") (pin "1") (pinfunction "1_1") (pintype "passive"))
      (node (ref "C27") (pin "1") (pinfunction "1_1") (pintype "passive"))
      (node (ref "C28") (pin "1") (pinfunction "1_1") (pintype "passive"))
      (node (ref "C29") (pin "1") (pinfunction "1_1") (pintype "passive"))
      (node (ref "C3") (pin "1") (pinfunction "1_1") (pintype "passive"))
      (node (ref "C30") (pin "1") (pinfunction "1_1") (pintype "passive"))
      (node (ref "C31") (pin "1") (pinfunction "1_1") (pintype "passive"))
      (node (ref "C32") (pin "1") (pinfunction "1_1") (pintype "passive"))
      (node (ref "C33") (pin "1") (pinfunction "1_1") (pintype "passive"))
      (node (ref "C4") (pin "1") (pinfunction "1_1") (pintype "passive"))
      (node (ref "C5") (pin "2") (pinfunction "2_2") (pintype "passive"))
      (node (ref "C6") (pin "2") (pinfunction "2_2") (pintype "passive"))
      (node (ref "C7") (pin "1") (pinfunction "1_1") (pintype "passive"))
      (node (ref "C8") (pin "1") (pinfunction "1_1") (pintype "passive"))
      (node (ref "C9") (pin "1") (pinfunction "1_1") (pintype "passive"))
      (node (ref "D1") (pin "1") (pinfunction "Cathode_1") (pintype "passive"))
      (node (ref "J1") (pin "6") (pinfunction "6_6") (pintype "passive"))
      (node (ref "J1") (pin "7") (pinfunction "7_7") (pintype "passive"))
      (node (ref "J4") (pin "7") (pinfunction "7_7") (pintype "passive"))
      (node (ref "J5") (pin "6") (pinfunction "6_6") (pintype "passive"))
      (node (ref "J6") (pin "6") (pinfunction "6_6") (pintype "passive"))
      (node (ref "J7") (pin "10") (pinfunction "10_10") (pintype "passive"))
      (node (ref "J7") (pin "11") (pinfunction "11_11") (pintype "passive"))
      (node (ref "J7") (pin "5") (pinfunction "5_5") (pintype "passive"))
      (node (ref "J7") (pin "6") (pinfunction "6_6") (pintype "passive"))
      (node (ref "J7") (pin "7") (pinfunction "7_7") (pintype "passive"))
      (node (ref "J7") (pin "8") (pinfunction "8_8") (pintype "passive"))
      (node (ref "J7") (pin "9") (pinfunction "9_9") (pintype "passive"))
      (node (ref "L3") (pin "1") (pinfunction "1_1") (pintype "passive"))
      (node (ref "MH1") (pin "1") (pinfunction "1_1") (pintype "passive"))
      (node (ref "MH2") (pin "1") (pinfunction "1_1") (pintype "passive"))
      (node (ref "MH3") (pin "1") (pinfunction "1_1") (pintype "passive"))
      (node (ref "R13") (pin "1") (pinfunction "1_1") (pintype "passive"))
      (node (ref "R9") (pin "2") (pinfunction "2_2") (pintype "passive"))
      (node (ref "SW1") (pin "1") (pinfunction "1_1") (pintype "passive"))
      (node (ref "SW1") (pin "2") (pinfunction "2_2") (pintype "passive"))
      (node (ref "SW2") (pin "1") (pinfunction "1_1") (pintype "passive"))
      (node (ref "SW2") (pin "2") (pinfunction "2_2") (pintype "passive"))
      (node (ref "U1") (pin "22") (pinfunction "AGND_22") (pintype "passive"))
      (node (ref "U1") (pin "8") (pinfunction "GND_8") (pintype "passive"))
      (node (ref "U2") (pin "28") (pinfunction "UGND_28") (pintype "passive"))
      (node (ref "U2") (pin "3") (pinfunction "GND_3") (pintype "passive"))
      (node (ref "U3") (pin "3") (pinfunction "GND_3") (pintype "passive"))
      (node (ref "U3") (pin "6") (pinfunction "EPAD_6") (pintype "passive"))
      (node (ref "U4") (pin "3") (pinfunction "3_3") (pintype "passive"))
      (node (ref "U5") (pin "3") (pinfunction "3_3") (pintype "passive"))
      (node (ref "U6") (pin "3") (pinfunction "3_3") (pintype "passive"))
      (node (ref "U7") (pin "3") (pinfunction "3_3") (pintype "passive"))
      (node (ref "Z1") (pin "1") (pinfunction "1_1") (pintype "passive"))
      (node (ref "Z2") (pin "1") (pinfunction "1_1") (pintype "passive"))
    )
    (net (code "62") (name "Net-(C11-Pad1)") (class "Default")
      (node (ref "C11") (pin "1") (pinfunction "1_1") (pintype "passive"))
      (node (ref "JP1") (pin "1") (pinfunction "1_1") (pintype "passive"))
    )
    (net (code "63") (name "Net-(D1-Anode)") (class "Default")
      (node (ref "D1") (pin "2") (pinfunction "Anode_2") (pintype "passive"))
      (node (ref "R19") (pin "1") (pinfunction "1_1") (pintype "passive"))
    )
    (net (code "64") (name "Net-(D2-Anode)") (class "Default")
      (node (ref "D2") (pin "2") (pinfunction "Anode_2") (pintype "passive"))
      (node (ref "R18") (pin "1") (pinfunction "1_1") (pintype "passive"))
    )
    (net (code "65") (name "Net-(D2-Cathode)") (class "Default")
      (node (ref "D2") (pin "1") (pinfunction "Cathode_1") (pintype "passive"))
      (node (ref "U4") (pin "4") (pinfunction "4_4") (pintype "passive"))
    )
    (net (code "66") (name "Net-(D3-Anode)") (class "Default")
      (node (ref "D3") (pin "2") (pinfunction "Anode_2") (pintype "passive"))
      (node (ref "R2") (pin "1") (pinfunction "1_1") (pintype "passive"))
    )
    (net (code "67") (name "Net-(D4-Anode)") (class "Default")
      (node (ref "D4") (pin "2") (pinfunction "Anode_2") (pintype "passive"))
      (node (ref "R3") (pin "1") (pinfunction "1_1") (pintype "passive"))
    )
    (net (code "68") (name "Net-(D5-Anode)") (class "Default")
      (node (ref "D5") (pin "2") (pinfunction "Anode_2") (pintype "passive"))
      (node (ref "R28") (pin "1") (pinfunction "1_1") (pintype "passive"))
    )
    (net (code "69") (name "Net-(D6-Anode)") (class "Default")
      (node (ref "D6") (pin "2") (pinfunction "Anode_2") (pintype "passive"))
      (node (ref "R26") (pin "1") (pinfunction "1_1") (pintype "passive"))
    )
    (net (code "70") (name "Net-(J7-Pad4)") (class "Default")
      (node (ref "J7") (pin "4") (pinfunction "4_4") (pintype "passive"))
      (node (ref "R9") (pin "1") (pinfunction "1_1") (pintype "passive"))
    )
    (net (code "71") (name "Net-(JP1-Pad3)") (class "Default")
      (node (ref "JP1") (pin "3") (pinfunction "3_3") (pintype "passive"))
      (node (ref "R13") (pin "2") (pinfunction "2_2") (pintype "passive"))
    )
    (net (code "72") (name "Net-(R25-Pad2)") (class "Default")
      (node (ref "R25") (pin "2") (pinfunction "2_2") (pintype "passive"))
      (node (ref "U7") (pin "4") (pinfunction "4_4") (pintype "passive"))
    )
    (net (code "73") (name "unconnected-(J1-Pad1)") (class "Default")
      (node (ref "J1") (pin "1") (pinfunction "1_1") (pintype "passive+no_connect"))
    )
    (net (code "74") (name "unconnected-(J1-Pad8)") (class "Default")
      (node (ref "J1") (pin "8") (pinfunction "8_8") (pintype "passive+no_connect"))
    )
    (net (code "75") (name "unconnected-(MH4-Pad1)") (class "Default")
      (node (ref "MH4") (pin "1") (pinfunction "1_1") (pintype "passive+no_connect"))
    )
    (net (code "76") (name "unconnected-(R24-Pad1)") (class "Default")
      (node (ref "R24") (pin "1") (pinfunction "1_1") (pintype "passive"))
    )
    (net (code "77") (name "unconnected-(U2-(AIN0{slash}INT1)PD1-Pad7)") (class "Default")
      (node (ref "U2") (pin "7") (pinfunction "(AIN0/INT1)PD1_7") (pintype "passive+no_connect"))
    )
    (net (code "78") (name "unconnected-(U2-(AIN2{slash}PCINT11)PC2-Pad5)") (class "Default")
      (node (ref "U2") (pin "5") (pinfunction "(AIN2/PCINT11)PC2_5") (pintype "passive+no_connect"))
    )
    (net (code "79") (name "unconnected-(U2-(INT4{slash}ICP1{slash}CLK0)PC7-Pad22)") (class "Default")
      (node (ref "U2") (pin "22") (pinfunction "(INT4/ICP1/CLK0)PC7_22") (pintype "passive+no_connect"))
    )
    (net (code "80") (name "unconnected-(U2-(OC0B{slash}INT0)PD0-Pad6)") (class "Default")
      (node (ref "U2") (pin "6") (pinfunction "(OC0B/INT0)PD0_6") (pintype "passive+no_connect"))
    )
    (net (code "81") (name "unconnected-(U2-(OC1A{slash}PCINT8)PC6-Pad23)") (class "Default")
      (node (ref "U2") (pin "23") (pinfunction "(OC1A/PCINT8)PC6_23") (pintype "passive+no_connect"))
    )
    (net (code "82") (name "unconnected-(U2-(PCINT9{slash}OC1B)PC5-Pad25)") (class "Default")
      (node (ref "U2") (pin "25") (pinfunction "(PCINT9/OC1B)PC5_25") (pintype "passive+no_connect"))
    )
    (net (code "83") (name "unconnected-(U2-(PCINT10)PC4-Pad26)") (class "Default")
      (node (ref "U2") (pin "26") (pinfunction "(PCINT10)PC4_26") (pintype "passive+no_connect"))
    )
    (net (code "84") (name "unconnected-(U2-(RTS{slash}AIN5{slash}INT6)PD6-Pad12)") (class "Default")
      (node (ref "U2") (pin "12") (pinfunction "(RTS/AIN5/INT6)PD6_12") (pintype "passive"))
    )
    (net (code "85") (name "unconnected-(U2-(SS{slash}PCINT0)PB0-Pad14)") (class "Default")
      (node (ref "U2") (pin "14") (pinfunction "(SS/PCINT0)PB0_14") (pintype "passive+no_connect"))
    )
  )
)
